# KranPowerV1_3.net
KiCad netlist of a schematic drawn in EAGLE
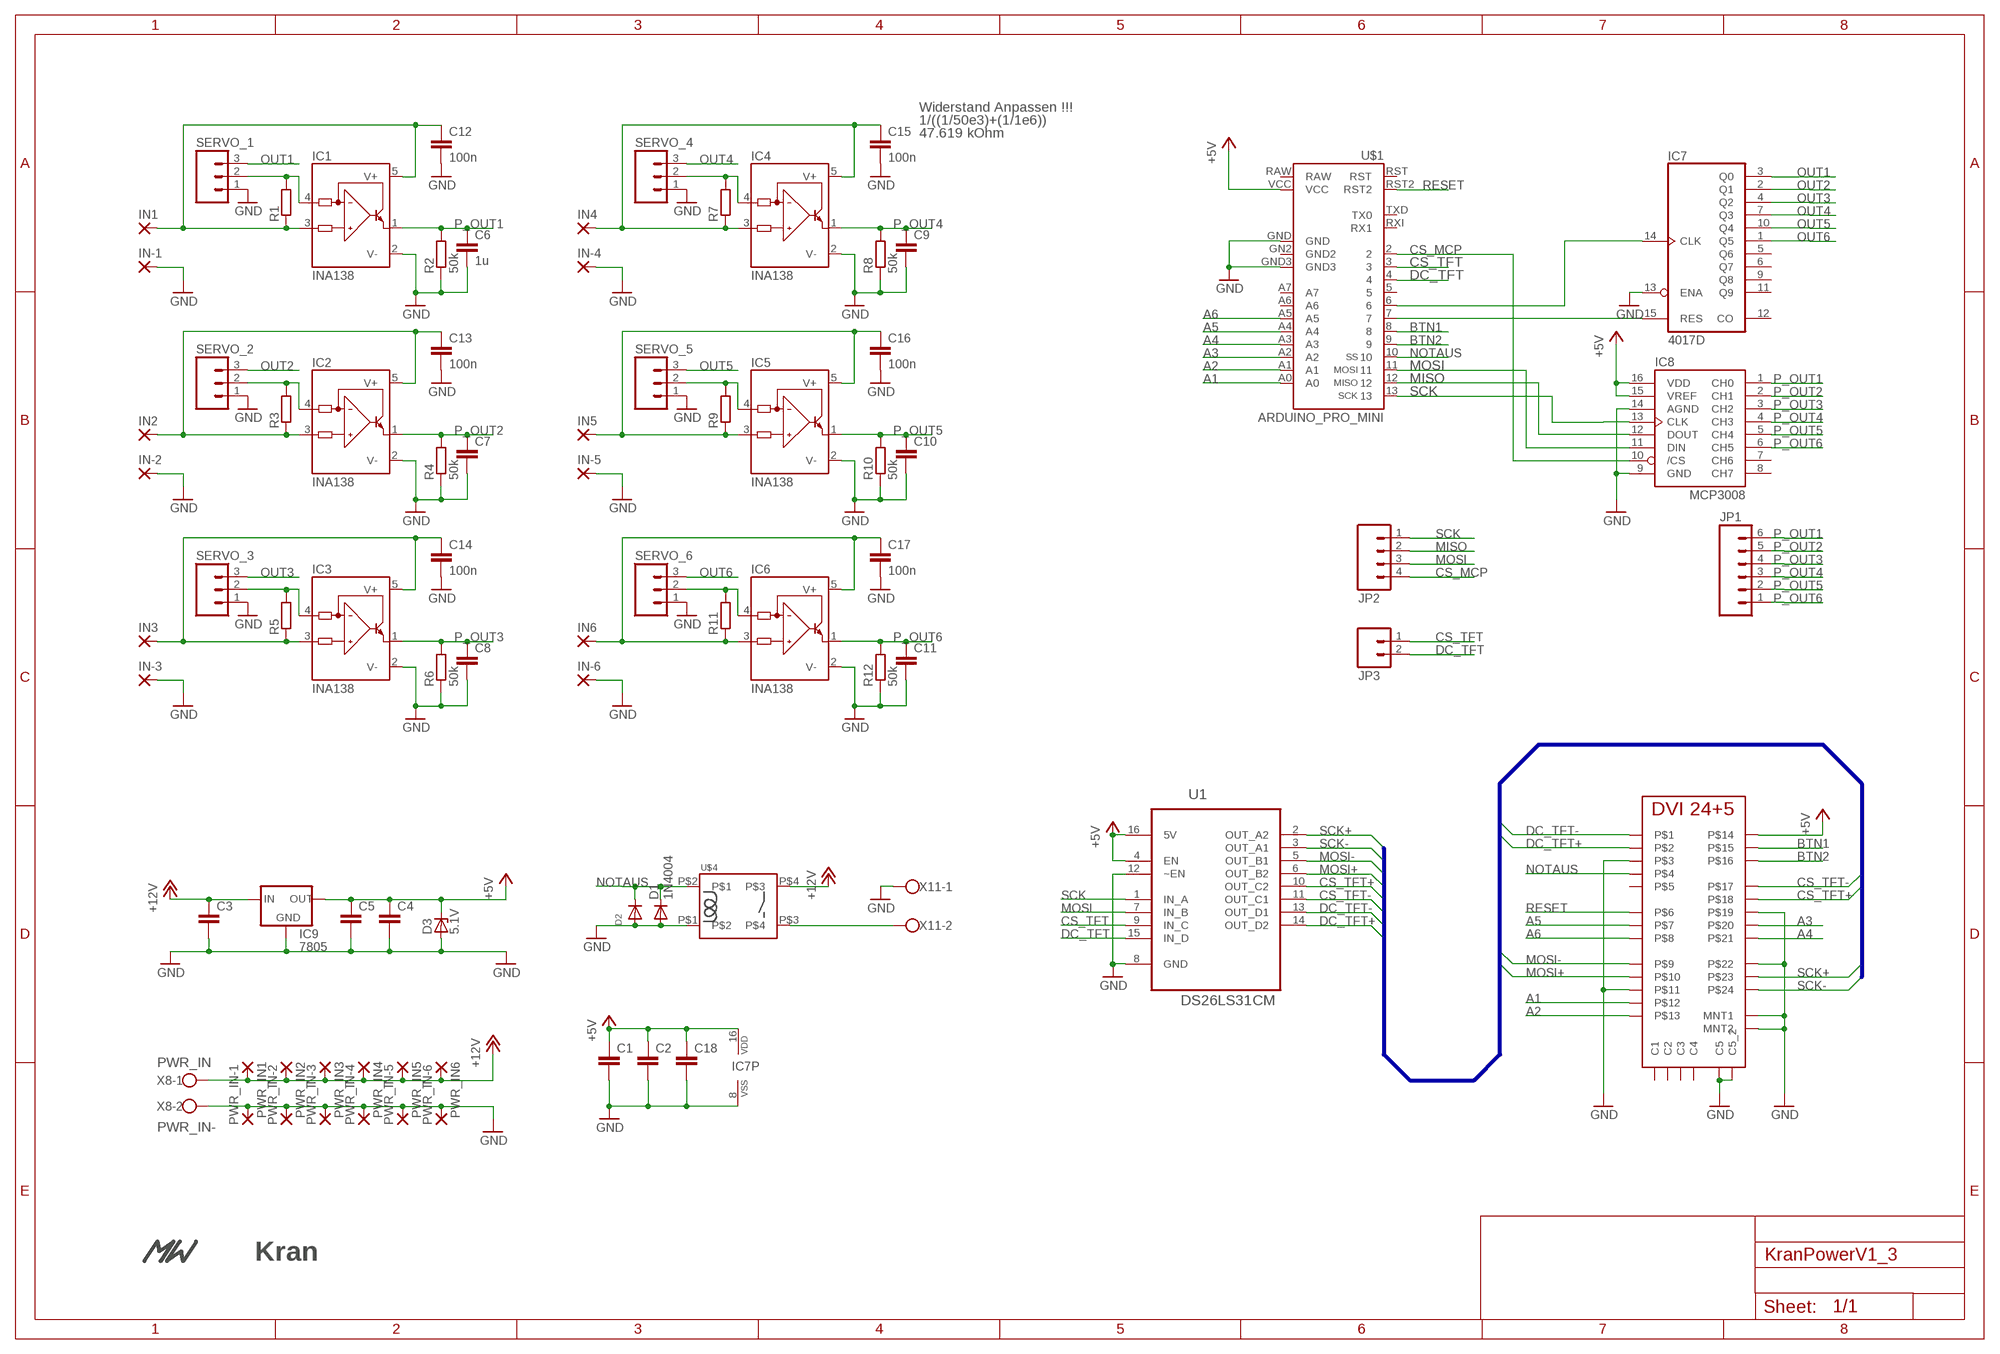
[diagram p0: schematic, sheet 1]

(export (version "E")
  (design (tool "Eeschema 10.0.6"))
  (components
    (comp (ref "C1")
      (value "C-EUC0603")
      (footprint "eagle-import:C0603")
      (libsource (lib "eagle-import") (part "C-EUC0603"))
    )
    (comp (ref "C2")
      (value "C-EUC0603")
      (footprint "eagle-import:C0603")
      (libsource (lib "eagle-import") (part "C-EUC0603"))
    )
    (comp (ref "C3")
      (value "C-EUC0603")
      (footprint "eagle-import:C0603")
      (libsource (lib "eagle-import") (part "C-EUC0603"))
    )
    (comp (ref "C4")
      (value "C-EUC0603")
      (footprint "eagle-import:C0603")
      (libsource (lib "eagle-import") (part "C-EUC0603"))
    )
    (comp (ref "C5")
      (value "C-EUC1206")
      (footprint "eagle-import:C1206")
      (libsource (lib "eagle-import") (part "C-EUC1206"))
    )
    (comp (ref "C6")
      (value "1u")
      (footprint "eagle-import:C0603")
      (libsource (lib "eagle-import") (part "C-EUC0603"))
    )
    (comp (ref "C7")
      (value "C-EUC0603")
      (footprint "eagle-import:C0603")
      (libsource (lib "eagle-import") (part "C-EUC0603"))
    )
    (comp (ref "C8")
      (value "C-EUC0603")
      (footprint "eagle-import:C0603")
      (libsource (lib "eagle-import") (part "C-EUC0603"))
    )
    (comp (ref "C9")
      (value "C-EUC0603")
      (footprint "eagle-import:C0603")
      (libsource (lib "eagle-import") (part "C-EUC0603"))
    )
    (comp (ref "C10")
      (value "C-EUC0603")
      (footprint "eagle-import:C0603")
      (libsource (lib "eagle-import") (part "C-EUC0603"))
    )
    (comp (ref "C11")
      (value "C-EUC0603")
      (footprint "eagle-import:C0603")
      (libsource (lib "eagle-import") (part "C-EUC0603"))
    )
    (comp (ref "C12")
      (value "100n")
      (footprint "eagle-import:C0603")
      (libsource (lib "eagle-import") (part "C-EUC0603"))
    )
    (comp (ref "C13")
      (value "100n")
      (footprint "eagle-import:C0603")
      (libsource (lib "eagle-import") (part "C-EUC0603"))
    )
    (comp (ref "C14")
      (value "100n")
      (footprint "eagle-import:C0603")
      (libsource (lib "eagle-import") (part "C-EUC0603"))
    )
    (comp (ref "C15")
      (value "100n")
      (footprint "eagle-import:C0603")
      (libsource (lib "eagle-import") (part "C-EUC0603"))
    )
    (comp (ref "C16")
      (value "100n")
      (footprint "eagle-import:C0603")
      (libsource (lib "eagle-import") (part "C-EUC0603"))
    )
    (comp (ref "C17")
      (value "100n")
      (footprint "eagle-import:C0603")
      (libsource (lib "eagle-import") (part "C-EUC0603"))
    )
    (comp (ref "C18")
      (value "C-EUC0603")
      (footprint "eagle-import:C0603")
      (libsource (lib "eagle-import") (part "C-EUC0603"))
    )
    (comp (ref "D1")
      (value "1N4004")
      (footprint "eagle-import:DO41-10")
      (libsource (lib "eagle-import") (part "1N4004"))
    )
    (comp (ref "D2")
      (value "DIODESMA")
      (footprint "eagle-import:SMADIODE")
      (libsource (lib "eagle-import") (part "DIODESMA"))
    )
    (comp (ref "D3")
      (value "5.1V")
      (footprint "eagle-import:DO34Z7")
      (libsource (lib "eagle-import") (part "ZENER-DIODEDO34-7"))
    )
    (comp (ref "IC1")
      (value "INA138")
      (footprint "eagle-import:SOT23-5")
      (fields (field (name "MF") "TEXAS INSTRUMENTS") (field (name "MPN") "INA138NA/250"))
      (libsource (lib "eagle-import") (part "INA138"))
    )
    (comp (ref "IC2")
      (value "INA138")
      (footprint "eagle-import:SOT23-5")
      (fields (field (name "MF") "TEXAS INSTRUMENTS") (field (name "MPN") "INA138NA/250"))
      (libsource (lib "eagle-import") (part "INA138"))
    )
    (comp (ref "IC3")
      (value "INA138")
      (footprint "eagle-import:SOT23-5")
      (fields (field (name "MF") "TEXAS INSTRUMENTS") (field (name "MPN") "INA138NA/250"))
      (libsource (lib "eagle-import") (part "INA138"))
    )
    (comp (ref "IC4")
      (value "INA138")
      (footprint "eagle-import:SOT23-5")
      (fields (field (name "MF") "TEXAS INSTRUMENTS") (field (name "MPN") "INA138NA/250"))
      (libsource (lib "eagle-import") (part "INA138"))
    )
    (comp (ref "IC5")
      (value "INA138")
      (footprint "eagle-import:SOT23-5")
      (fields (field (name "MF") "TEXAS INSTRUMENTS") (field (name "MPN") "INA138NA/250"))
      (libsource (lib "eagle-import") (part "INA138"))
    )
    (comp (ref "IC6")
      (value "INA138")
      (footprint "eagle-import:SOT23-5")
      (fields (field (name "MF") "TEXAS INSTRUMENTS") (field (name "MPN") "INA138NA/250"))
      (libsource (lib "eagle-import") (part "INA138"))
    )
    (comp (ref "IC7")
      (value "4017D")
      (footprint "eagle-import:SO16")
      (libsource (lib "eagle-import") (part "4017D"))
    )
    (comp (ref "IC8")
      (value "MCP3008")
      (footprint "eagle-import:SO16")
      (libsource (lib "eagle-import") (part "MCP3008"))
    )
    (comp (ref "IC9")
      (value "7805")
      (footprint "eagle-import:78XXL")
      (libsource (lib "eagle-import") (part "V_REG_78XXSIDE"))
    )
    (comp (ref "IN-1")
      (value "3,81/1,3")
      (footprint "eagle-import:3,81_1,3")
      (libsource (lib "eagle-import") (part "3,81/1,3"))
    )
    (comp (ref "IN-2")
      (value "3,81/1,3")
      (footprint "eagle-import:3,81_1,3")
      (libsource (lib "eagle-import") (part "3,81/1,3"))
    )
    (comp (ref "IN-3")
      (value "3,81/1,3")
      (footprint "eagle-import:3,81_1,3")
      (libsource (lib "eagle-import") (part "3,81/1,3"))
    )
    (comp (ref "IN-4")
      (value "3,81/1,3")
      (footprint "eagle-import:3,81_1,3")
      (libsource (lib "eagle-import") (part "3,81/1,3"))
    )
    (comp (ref "IN-5")
      (value "3,81/1,3")
      (footprint "eagle-import:3,81_1,3")
      (libsource (lib "eagle-import") (part "3,81/1,3"))
    )
    (comp (ref "IN-6")
      (value "3,81/1,3")
      (footprint "eagle-import:3,81_1,3")
      (libsource (lib "eagle-import") (part "3,81/1,3"))
    )
    (comp (ref "IN1")
      (value "3,81/1,3")
      (footprint "eagle-import:3,81_1,3")
      (libsource (lib "eagle-import") (part "3,81/1,3"))
    )
    (comp (ref "IN2")
      (value "3,81/1,3")
      (footprint "eagle-import:3,81_1,3")
      (libsource (lib "eagle-import") (part "3,81/1,3"))
    )
    (comp (ref "IN3")
      (value "3,81/1,3")
      (footprint "eagle-import:3,81_1,3")
      (libsource (lib "eagle-import") (part "3,81/1,3"))
    )
    (comp (ref "IN4")
      (value "3,81/1,3")
      (footprint "eagle-import:3,81_1,3")
      (libsource (lib "eagle-import") (part "3,81/1,3"))
    )
    (comp (ref "IN5")
      (value "3,81/1,3")
      (footprint "eagle-import:3,81_1,3")
      (libsource (lib "eagle-import") (part "3,81/1,3"))
    )
    (comp (ref "IN6")
      (value "3,81/1,3")
      (footprint "eagle-import:3,81_1,3")
      (libsource (lib "eagle-import") (part "3,81/1,3"))
    )
    (comp (ref "JP1")
      (value "M06LOCK")
      (footprint "eagle-import:1X06_LOCK")
      (libsource (lib "eagle-import") (part "M06LOCK"))
    )
    (comp (ref "JP2")
      (value "M04LOCK")
      (footprint "eagle-import:1X04_LOCK")
      (libsource (lib "eagle-import") (part "M04LOCK"))
    )
    (comp (ref "JP3")
      (value "M02LOCK")
      (footprint "eagle-import:1X02_LOCK")
      (libsource (lib "eagle-import") (part "M02LOCK"))
    )
    (comp (ref "PWR_IN-1")
      (value "3,81/1,3")
      (footprint "eagle-import:3,81_1,3")
      (libsource (lib "eagle-import") (part "3,81/1,3"))
    )
    (comp (ref "PWR_IN-2")
      (value "3,81/1,3")
      (footprint "eagle-import:3,81_1,3")
      (libsource (lib "eagle-import") (part "3,81/1,3"))
    )
    (comp (ref "PWR_IN-3")
      (value "3,81/1,3")
      (footprint "eagle-import:3,81_1,3")
      (libsource (lib "eagle-import") (part "3,81/1,3"))
    )
    (comp (ref "PWR_IN-4")
      (value "3,81/1,3")
      (footprint "eagle-import:3,81_1,3")
      (libsource (lib "eagle-import") (part "3,81/1,3"))
    )
    (comp (ref "PWR_IN-5")
      (value "3,81/1,3")
      (footprint "eagle-import:3,81_1,3")
      (libsource (lib "eagle-import") (part "3,81/1,3"))
    )
    (comp (ref "PWR_IN-6")
      (value "3,81/1,3")
      (footprint "eagle-import:3,81_1,3")
      (libsource (lib "eagle-import") (part "3,81/1,3"))
    )
    (comp (ref "PWR_IN1")
      (value "3,81/1,3")
      (footprint "eagle-import:3,81_1,3")
      (libsource (lib "eagle-import") (part "3,81/1,3"))
    )
    (comp (ref "PWR_IN2")
      (value "3,81/1,3")
      (footprint "eagle-import:3,81_1,3")
      (libsource (lib "eagle-import") (part "3,81/1,3"))
    )
    (comp (ref "PWR_IN3")
      (value "3,81/1,3")
      (footprint "eagle-import:3,81_1,3")
      (libsource (lib "eagle-import") (part "3,81/1,3"))
    )
    (comp (ref "PWR_IN4")
      (value "3,81/1,3")
      (footprint "eagle-import:3,81_1,3")
      (libsource (lib "eagle-import") (part "3,81/1,3"))
    )
    (comp (ref "PWR_IN5")
      (value "3,81/1,3")
      (footprint "eagle-import:3,81_1,3")
      (libsource (lib "eagle-import") (part "3,81/1,3"))
    )
    (comp (ref "PWR_IN6")
      (value "3,81/1,3")
      (footprint "eagle-import:3,81_1,3")
      (libsource (lib "eagle-import") (part "3,81/1,3"))
    )
    (comp (ref "R1")
      (value "R-EU_R2512")
      (footprint "eagle-import:R2512")
      (libsource (lib "eagle-import") (part "R-EU_R2512"))
    )
    (comp (ref "R2")
      (value "50k")
      (footprint "eagle-import:R0603")
      (libsource (lib "eagle-import") (part "R-EU_R0603"))
    )
    (comp (ref "R3")
      (value "R-EU_R2512")
      (footprint "eagle-import:R2512")
      (libsource (lib "eagle-import") (part "R-EU_R2512"))
    )
    (comp (ref "R4")
      (value "50k")
      (footprint "eagle-import:R0603")
      (libsource (lib "eagle-import") (part "R-EU_R0603"))
    )
    (comp (ref "R5")
      (value "R-EU_R2512")
      (footprint "eagle-import:R2512")
      (libsource (lib "eagle-import") (part "R-EU_R2512"))
    )
    (comp (ref "R6")
      (value "50k")
      (footprint "eagle-import:R0603")
      (libsource (lib "eagle-import") (part "R-EU_R0603"))
    )
    (comp (ref "R7")
      (value "R-EU_R2512")
      (footprint "eagle-import:R2512")
      (libsource (lib "eagle-import") (part "R-EU_R2512"))
    )
    (comp (ref "R8")
      (value "50k")
      (footprint "eagle-import:R0603")
      (libsource (lib "eagle-import") (part "R-EU_R0603"))
    )
    (comp (ref "R9")
      (value "R-EU_R2512")
      (footprint "eagle-import:R2512")
      (libsource (lib "eagle-import") (part "R-EU_R2512"))
    )
    (comp (ref "R10")
      (value "50k")
      (footprint "eagle-import:R0603")
      (libsource (lib "eagle-import") (part "R-EU_R0603"))
    )
    (comp (ref "R11")
      (value "R-EU_R2512")
      (footprint "eagle-import:R2512")
      (libsource (lib "eagle-import") (part "R-EU_R2512"))
    )
    (comp (ref "R12")
      (value "50k")
      (footprint "eagle-import:R0603")
      (libsource (lib "eagle-import") (part "R-EU_R0603"))
    )
    (comp (ref "SERVO_1")
      (value "M03LOCK")
      (footprint "eagle-import:1X03_LOCK")
      (libsource (lib "eagle-import") (part "M03LOCK"))
    )
    (comp (ref "SERVO_2")
      (value "M03LOCK")
      (footprint "eagle-import:1X03_LOCK")
      (libsource (lib "eagle-import") (part "M03LOCK"))
    )
    (comp (ref "SERVO_3")
      (value "M03LOCK")
      (footprint "eagle-import:1X03_LOCK")
      (libsource (lib "eagle-import") (part "M03LOCK"))
    )
    (comp (ref "SERVO_4")
      (value "M03LOCK")
      (footprint "eagle-import:1X03_LOCK")
      (libsource (lib "eagle-import") (part "M03LOCK"))
    )
    (comp (ref "SERVO_5")
      (value "M03LOCK")
      (footprint "eagle-import:1X03_LOCK")
      (libsource (lib "eagle-import") (part "M03LOCK"))
    )
    (comp (ref "SERVO_6")
      (value "M03LOCK")
      (footprint "eagle-import:1X03_LOCK")
      (libsource (lib "eagle-import") (part "M03LOCK"))
    )
    (comp (ref "U$1")
      (value "ARDUINO_PRO_MINI")
      (footprint "eagle-import:ARDUINO_PRO_MINI")
      (libsource (lib "eagle-import") (part "ARDUINO_PRO_MINI"))
    )
    (comp (ref "U$2")
      (value "MW_LOGO")
      (footprint "eagle-import:MW_11X5MM")
      (libsource (lib "eagle-import") (part "MW_LOGO"))
    )
    (comp (ref "U$3")
      (value "KRAN_LOGO")
      (footprint "eagle-import:KRAN_LOGO")
      (libsource (lib "eagle-import") (part "KRAN_LOGO"))
    )
    (comp (ref "U$4")
      (value "RELAY_ZETTLER_AZ767")
      (footprint "eagle-import:RELAY_ZETTLER_AZ767")
      (libsource (lib "eagle-import") (part "RELAY_ZETTLER_AZ767"))
    )
    (comp (ref "U$11")
      (value "DVI_BUCHSE")
      (footprint "eagle-import:DVI_BUCHSE")
      (libsource (lib "eagle-import") (part "DVI_BUCHSE"))
    )
    (comp (ref "U1")
      (value "DS26LS31CM")
      (footprint "eagle-import:SOIC127P600X175-16N")
      (libsource (lib "eagle-import") (part "DS26LS31CM"))
    )
    (comp (ref "X8")
      (value "W237-102")
      (footprint "eagle-import:W237-102")
      (fields (field (name "MPN") "237-102"))
      (libsource (lib "eagle-import") (part "W237-102"))
    )
    (comp (ref "X11")
      (value "W237-102")
      (footprint "eagle-import:W237-102")
      (fields (field (name "MPN") "237-102"))
      (libsource (lib "eagle-import") (part "W237-102"))
    )
  )
  (nets
    (net (code "1") (name "+5V") (class "Default")
      (node (ref "C1") (pin "1") (pinfunction "1_1") (pintype "passive"))
      (node (ref "C18") (pin "1") (pinfunction "1_1") (pintype "passive"))
      (node (ref "C2") (pin "1") (pinfunction "1_1") (pintype "passive"))
      (node (ref "C4") (pin "1") (pinfunction "1_1") (pintype "passive"))
      (node (ref "C5") (pin "1") (pinfunction "1_1") (pintype "passive"))
      (node (ref "D3") (pin "C") (pinfunction "C_C") (pintype "passive"))
      (node (ref "IC7") (pin "16") (pinfunction "VDD_16") (pintype "power_in"))
      (node (ref "IC8") (pin "15") (pinfunction "VREF_15") (pintype "input"))
      (node (ref "IC8") (pin "16") (pinfunction "VDD_16") (pintype "power_in"))
      (node (ref "IC9") (pin "OUT") (pinfunction "OUT_OUT") (pintype "output"))
      (node (ref "U$1") (pin "VCC") (pinfunction "VCC_VCC") (pintype "bidirectional"))
      (node (ref "U$11") (pin "P$14") (pinfunction "P$14_P$14") (pintype "bidirectional"))
      (node (ref "U1") (pin "16") (pinfunction "5V_16") (pintype "power_in"))
      (node (ref "U1") (pin "4") (pinfunction "EN_4") (pintype "input"))
    )
    (net (code "2") (name "+12V") (class "Default")
      (node (ref "C3") (pin "1") (pinfunction "1_1") (pintype "passive"))
      (node (ref "IC9") (pin "IN") (pinfunction "IN_IN") (pintype "input"))
      (node (ref "PWR_IN1") (pin "1") (pinfunction "P_1") (pintype "passive"))
      (node (ref "PWR_IN2") (pin "1") (pinfunction "P_1") (pintype "passive"))
      (node (ref "PWR_IN3") (pin "1") (pinfunction "P_1") (pintype "passive"))
      (node (ref "PWR_IN4") (pin "1") (pinfunction "P_1") (pintype "passive"))
      (node (ref "PWR_IN5") (pin "1") (pinfunction "P_1") (pintype "passive"))
      (node (ref "PWR_IN6") (pin "1") (pinfunction "P_1") (pintype "passive"))
      (node (ref "U$4") (pin "P$4") (pinfunction "P$3_P$4") (pintype "bidirectional"))
      (node (ref "X8") (pin "1") (pinfunction "KL_1") (pintype "passive"))
    )
    (net (code "3") (name "/A1") (class "Default")
      (node (ref "U$1") (pin "A0") (pinfunction "A0_A0") (pintype "bidirectional"))
      (node (ref "U$11") (pin "P$12") (pinfunction "P$12_P$12") (pintype "bidirectional"))
    )
    (net (code "4") (name "/A2") (class "Default")
      (node (ref "U$1") (pin "A1") (pinfunction "A1_A1") (pintype "bidirectional"))
      (node (ref "U$11") (pin "P$13") (pinfunction "P$13_P$13") (pintype "bidirectional"))
    )
    (net (code "5") (name "/A3") (class "Default")
      (node (ref "U$1") (pin "A2") (pinfunction "A2_A2") (pintype "bidirectional"))
      (node (ref "U$11") (pin "P$4") (pinfunction "P$20_P$4") (pintype "bidirectional"))
    )
    (net (code "6") (name "/A4") (class "Default")
      (node (ref "U$1") (pin "A3") (pinfunction "A3_A3") (pintype "bidirectional"))
      (node (ref "U$11") (pin "P$5") (pinfunction "P$21_P$5") (pintype "bidirectional"))
    )
    (net (code "7") (name "/A5") (class "Default")
      (node (ref "U$1") (pin "A4") (pinfunction "A4_A4") (pintype "bidirectional"))
      (node (ref "U$11") (pin "P$23") (pinfunction "P$7_P$23") (pintype "bidirectional"))
    )
    (net (code "8") (name "/A6") (class "Default")
      (node (ref "U$1") (pin "A5") (pinfunction "A5_A5") (pintype "bidirectional"))
      (node (ref "U$11") (pin "P$24") (pinfunction "P$8_P$24") (pintype "bidirectional"))
    )
    (net (code "9") (name "/BTN1") (class "Default")
      (node (ref "U$1") (pin "8") (pinfunction "8_8") (pintype "bidirectional"))
      (node (ref "U$11") (pin "P$15") (pinfunction "P$15_P$15") (pintype "bidirectional"))
    )
    (net (code "10") (name "/BTN2") (class "Default")
      (node (ref "U$1") (pin "9") (pinfunction "9_9") (pintype "bidirectional"))
      (node (ref "U$11") (pin "P$16") (pinfunction "P$16_P$16") (pintype "bidirectional"))
    )
    (net (code "11") (name "/CS_MCP") (class "Default")
      (node (ref "IC8") (pin "10") (pinfunction "/CS_10") (pintype "input"))
      (node (ref "JP2") (pin "4") (pinfunction "4_4") (pintype "passive"))
      (node (ref "U$1") (pin "2") (pinfunction "2_2") (pintype "bidirectional"))
    )
    (net (code "12") (name "/CS_TFT") (class "Default")
      (node (ref "JP3") (pin "1") (pinfunction "1_1") (pintype "passive"))
      (node (ref "U$1") (pin "3") (pinfunction "3_3") (pintype "bidirectional"))
      (node (ref "U1") (pin "9") (pinfunction "IN_C_9") (pintype "input"))
    )
    (net (code "13") (name "/CS_TFT+") (class "Default")
      (node (ref "U$11") (pin "P$2") (pinfunction "P$18_P$2") (pintype "bidirectional"))
      (node (ref "U1") (pin "10") (pinfunction "OUT_C2_10") (pintype "output"))
    )
    (net (code "14") (name "/CS_TFT-") (class "Default")
      (node (ref "U$11") (pin "P$1") (pinfunction "P$17_P$1") (pintype "bidirectional"))
      (node (ref "U1") (pin "11") (pinfunction "OUT_C1_11") (pintype "output"))
    )
    (net (code "15") (name "/DC_TFT") (class "Default")
      (node (ref "JP3") (pin "2") (pinfunction "2_2") (pintype "passive"))
      (node (ref "U$1") (pin "4") (pinfunction "4_4") (pintype "bidirectional"))
      (node (ref "U1") (pin "15") (pinfunction "IN_D_15") (pintype "input"))
    )
    (net (code "16") (name "/DC_TFT+") (class "Default")
      (node (ref "U$11") (pin "P$18") (pinfunction "P$2_P$18") (pintype "bidirectional"))
      (node (ref "U1") (pin "14") (pinfunction "OUT_D2_14") (pintype "output"))
    )
    (net (code "17") (name "/DC_TFT-") (class "Default")
      (node (ref "U$11") (pin "P$17") (pinfunction "P$1_P$17") (pintype "bidirectional"))
      (node (ref "U1") (pin "13") (pinfunction "OUT_D1_13") (pintype "output"))
    )
    (net (code "18") (name "/MISO") (class "Default")
      (node (ref "IC8") (pin "12") (pinfunction "DOUT_12") (pintype "output"))
      (node (ref "JP2") (pin "2") (pinfunction "2_2") (pintype "passive"))
      (node (ref "U$1") (pin "12") (pinfunction "12_12") (pintype "bidirectional"))
    )
    (net (code "19") (name "/MOSI") (class "Default")
      (node (ref "IC8") (pin "11") (pinfunction "DIN_11") (pintype "input"))
      (node (ref "JP2") (pin "3") (pinfunction "3_3") (pintype "passive"))
      (node (ref "U$1") (pin "11") (pinfunction "11_11") (pintype "bidirectional"))
      (node (ref "U1") (pin "7") (pinfunction "IN_B_7") (pintype "input"))
    )
    (net (code "20") (name "/MOSI+") (class "Default")
      (node (ref "U$11") (pin "P$10") (pinfunction "P$10_P$10") (pintype "bidirectional"))
      (node (ref "U1") (pin "6") (pinfunction "OUT_B2_6") (pintype "output"))
    )
    (net (code "21") (name "/MOSI-") (class "Default")
      (node (ref "U$11") (pin "P$9") (pinfunction "P$9_P$9") (pintype "bidirectional"))
      (node (ref "U1") (pin "5") (pinfunction "OUT_B1_5") (pintype "output"))
    )
    (net (code "22") (name "/NOTAUS") (class "Default")
      (node (ref "D1") (pin "C") (pinfunction "C_C") (pintype "passive"))
      (node (ref "D2") (pin "C") (pinfunction "C_C") (pintype "passive"))
      (node (ref "U$1") (pin "10") (pinfunction "10_10") (pintype "bidirectional"))
      (node (ref "U$11") (pin "P$20") (pinfunction "P$4_P$20") (pintype "bidirectional"))
      (node (ref "U$4") (pin "P$2") (pinfunction "P$1_P$2") (pintype "bidirectional"))
    )
    (net (code "23") (name "/OUT1") (class "Default")
      (node (ref "IC7") (pin "3") (pinfunction "Q0_3") (pintype "output"))
      (node (ref "SERVO_1") (pin "3") (pinfunction "3_3") (pintype "passive"))
    )
    (net (code "24") (name "/OUT2") (class "Default")
      (node (ref "IC7") (pin "2") (pinfunction "Q1_2") (pintype "output"))
      (node (ref "SERVO_2") (pin "3") (pinfunction "3_3") (pintype "passive"))
    )
    (net (code "25") (name "/OUT3") (class "Default")
      (node (ref "IC7") (pin "4") (pinfunction "Q2_4") (pintype "output"))
      (node (ref "SERVO_3") (pin "3") (pinfunction "3_3") (pintype "passive"))
    )
    (net (code "26") (name "/OUT4") (class "Default")
      (node (ref "IC7") (pin "7") (pinfunction "Q3_7") (pintype "output"))
      (node (ref "SERVO_4") (pin "3") (pinfunction "3_3") (pintype "passive"))
    )
    (net (code "27") (name "/OUT5") (class "Default")
      (node (ref "IC7") (pin "10") (pinfunction "Q4_10") (pintype "output"))
      (node (ref "SERVO_5") (pin "3") (pinfunction "3_3") (pintype "passive"))
    )
    (net (code "28") (name "/OUT6") (class "Default")
      (node (ref "IC7") (pin "1") (pinfunction "Q5_1") (pintype "output"))
      (node (ref "SERVO_6") (pin "3") (pinfunction "3_3") (pintype "passive"))
    )
    (net (code "29") (name "/P_OUT1") (class "Default")
      (node (ref "C6") (pin "1") (pinfunction "1_1") (pintype "passive"))
      (node (ref "IC1") (pin "1") (pinfunction "OUT_1") (pintype "output"))
      (node (ref "IC8") (pin "1") (pinfunction "CH0_1") (pintype "input"))
      (node (ref "JP1") (pin "6") (pinfunction "6_6") (pintype "passive"))
      (node (ref "R2") (pin "2") (pinfunction "2_2") (pintype "passive"))
    )
    (net (code "30") (name "/P_OUT2") (class "Default")
      (node (ref "C7") (pin "1") (pinfunction "1_1") (pintype "passive"))
      (node (ref "IC2") (pin "1") (pinfunction "OUT_1") (pintype "output"))
      (node (ref "IC8") (pin "2") (pinfunction "CH1_2") (pintype "input"))
      (node (ref "JP1") (pin "5") (pinfunction "5_5") (pintype "passive"))
      (node (ref "R4") (pin "2") (pinfunction "2_2") (pintype "passive"))
    )
    (net (code "31") (name "/P_OUT3") (class "Default")
      (node (ref "C8") (pin "1") (pinfunction "1_1") (pintype "passive"))
      (node (ref "IC3") (pin "1") (pinfunction "OUT_1") (pintype "output"))
      (node (ref "IC8") (pin "3") (pinfunction "CH2_3") (pintype "input"))
      (node (ref "JP1") (pin "4") (pinfunction "4_4") (pintype "passive"))
      (node (ref "R6") (pin "2") (pinfunction "2_2") (pintype "passive"))
    )
    (net (code "32") (name "/P_OUT4") (class "Default")
      (node (ref "C9") (pin "1") (pinfunction "1_1") (pintype "passive"))
      (node (ref "IC4") (pin "1") (pinfunction "OUT_1") (pintype "output"))
      (node (ref "IC8") (pin "4") (pinfunction "CH3_4") (pintype "input"))
      (node (ref "JP1") (pin "3") (pinfunction "3_3") (pintype "passive"))
      (node (ref "R8") (pin "2") (pinfunction "2_2") (pintype "passive"))
    )
    (net (code "33") (name "/P_OUT5") (class "Default")
      (node (ref "C10") (pin "1") (pinfunction "1_1") (pintype "passive"))
      (node (ref "IC5") (pin "1") (pinfunction "OUT_1") (pintype "output"))
      (node (ref "IC8") (pin "5") (pinfunction "CH4_5") (pintype "input"))
      (node (ref "JP1") (pin "2") (pinfunction "2_2") (pintype "passive"))
      (node (ref "R10") (pin "2") (pinfunction "2_2") (pintype "passive"))
    )
    (net (code "34") (name "/P_OUT6") (class "Default")
      (node (ref "C11") (pin "1") (pinfunction "1_1") (pintype "passive"))
      (node (ref "IC6") (pin "1") (pinfunction "OUT_1") (pintype "output"))
      (node (ref "IC8") (pin "6") (pinfunction "CH5_6") (pintype "input"))
      (node (ref "JP1") (pin "1") (pinfunction "1_1") (pintype "passive"))
      (node (ref "R12") (pin "2") (pinfunction "2_2") (pintype "passive"))
    )
    (net (code "35") (name "/RESET") (class "Default")
      (node (ref "U$1") (pin "RST2") (pinfunction "RST2_RST2") (pintype "bidirectional"))
      (node (ref "U$11") (pin "P$22") (pinfunction "P$6_P$22") (pintype "bidirectional"))
    )
    (net (code "36") (name "/SCK") (class "Default")
      (node (ref "IC8") (pin "13") (pinfunction "CLK_13") (pintype "input"))
      (node (ref "JP2") (pin "1") (pinfunction "1_1") (pintype "passive"))
      (node (ref "U$1") (pin "13") (pinfunction "13_13") (pintype "bidirectional"))
      (node (ref "U1") (pin "1") (pinfunction "IN_A_1") (pintype "input"))
    )
    (net (code "37") (name "/SCK+") (class "Default")
      (node (ref "U$11") (pin "P$7") (pinfunction "P$23_P$7") (pintype "bidirectional"))
      (node (ref "U1") (pin "2") (pinfunction "OUT_A2_2") (pintype "output"))
    )
    (net (code "38") (name "/SCK-") (class "Default")
      (node (ref "U$11") (pin "P$8") (pinfunction "P$24_P$8") (pintype "bidirectional"))
      (node (ref "U1") (pin "3") (pinfunction "OUT_A1_3") (pintype "output"))
    )
    (net (code "39") (name "GND") (class "Default")
      (node (ref "C1") (pin "2") (pinfunction "2_2") (pintype "passive"))
      (node (ref "C10") (pin "2") (pinfunction "2_2") (pintype "passive"))
      (node (ref "C11") (pin "2") (pinfunction "2_2") (pintype "passive"))
      (node (ref "C12") (pin "2") (pinfunction "2_2") (pintype "passive"))
      (node (ref "C13") (pin "2") (pinfunction "2_2") (pintype "passive"))
      (node (ref "C14") (pin "2") (pinfunction "2_2") (pintype "passive"))
      (node (ref "C15") (pin "2") (pinfunction "2_2") (pintype "passive"))
      (node (ref "C16") (pin "2") (pinfunction "2_2") (pintype "passive"))
      (node (ref "C17") (pin "2") (pinfunction "2_2") (pintype "passive"))
      (node (ref "C18") (pin "2") (pinfunction "2_2") (pintype "passive"))
      (node (ref "C2") (pin "2") (pinfunction "2_2") (pintype "passive"))
      (node (ref "C3") (pin "2") (pinfunction "2_2") (pintype "passive"))
      (node (ref "C4") (pin "2") (pinfunction "2_2") (pintype "passive"))
      (node (ref "C5") (pin "2") (pinfunction "2_2") (pintype "passive"))
      (node (ref "C6") (pin "2") (pinfunction "2_2") (pintype "passive"))
      (node (ref "C7") (pin "2") (pinfunction "2_2") (pintype "passive"))
      (node (ref "C8") (pin "2") (pinfunction "2_2") (pintype "passive"))
      (node (ref "C9") (pin "2") (pinfunction "2_2") (pintype "passive"))
      (node (ref "D1") (pin "A") (pinfunction "A_A") (pintype "passive"))
      (node (ref "D2") (pin "A") (pinfunction "A_A") (pintype "passive"))
      (node (ref "D3") (pin "A") (pinfunction "A_A") (pintype "passive"))
      (node (ref "IC1") (pin "2") (pinfunction "V-_2") (pintype "power_in"))
      (node (ref "IC2") (pin "2") (pinfunction "V-_2") (pintype "power_in"))
      (node (ref "IC3") (pin "2") (pinfunction "V-_2") (pintype "power_in"))
      (node (ref "IC4") (pin "2") (pinfunction "V-_2") (pintype "power_in"))
      (node (ref "IC5") (pin "2") (pinfunction "V-_2") (pintype "power_in"))
      (node (ref "IC6") (pin "2") (pinfunction "V-_2") (pintype "power_in"))
      (node (ref "IC7") (pin "13") (pinfunction "ENA_13") (pintype "input"))
      (node (ref "IC7") (pin "8") (pinfunction "VSS_8") (pintype "power_in"))
      (node (ref "IC8") (pin "14") (pinfunction "AGND_14") (pintype "power_in"))
      (node (ref "IC8") (pin "9") (pinfunction "GND_9") (pintype "power_in"))
      (node (ref "IC9") (pin "GND") (pinfunction "GND_GND") (pintype "input"))
      (node (ref "IN-1") (pin "1") (pinfunction "P_1") (pintype "passive"))
      (node (ref "IN-2") (pin "1") (pinfunction "P_1") (pintype "passive"))
      (node (ref "IN-3") (pin "1") (pinfunction "P_1") (pintype "passive"))
      (node (ref "IN-4") (pin "1") (pinfunction "P_1") (pintype "passive"))
      (node (ref "IN-5") (pin "1") (pinfunction "P_1") (pintype "passive"))
      (node (ref "IN-6") (pin "1") (pinfunction "P_1") (pintype "passive"))
      (node (ref "PWR_IN-1") (pin "1") (pinfunction "P_1") (pintype "passive"))
      (node (ref "PWR_IN-2") (pin "1") (pinfunction "P_1") (pintype "passive"))
      (node (ref "PWR_IN-3") (pin "1") (pinfunction "P_1") (pintype "passive"))
      (node (ref "PWR_IN-4") (pin "1") (pinfunction "P_1") (pintype "passive"))
      (node (ref "PWR_IN-5") (pin "1") (pinfunction "P_1") (pintype "passive"))
      (node (ref "PWR_IN-6") (pin "1") (pinfunction "P_1") (pintype "passive"))
      (node (ref "R10") (pin "1") (pinfunction "1_1") (pintype "passive"))
      (node (ref "R12") (pin "1") (pinfunction "1_1") (pintype "passive"))
      (node (ref "R2") (pin "1") (pinfunction "1_1") (pintype "passive"))
      (node (ref "R4") (pin "1") (pinfunction "1_1") (pintype "passive"))
      (node (ref "R6") (pin "1") (pinfunction "1_1") (pintype "passive"))
      (node (ref "R8") (pin "1") (pinfunction "1_1") (pintype "passive"))
      (node (ref "SERVO_1") (pin "1") (pinfunction "1_1") (pintype "passive"))
      (node (ref "SERVO_2") (pin "1") (pinfunction "1_1") (pintype "passive"))
      (node (ref "SERVO_3") (pin "1") (pinfunction "1_1") (pintype "passive"))
      (node (ref "SERVO_4") (pin "1") (pinfunction "1_1") (pintype "passive"))
      (node (ref "SERVO_5") (pin "1") (pinfunction "1_1") (pintype "passive"))
      (node (ref "SERVO_6") (pin "1") (pinfunction "1_1") (pintype "passive"))
      (node (ref "U$1") (pin "GND") (pinfunction "GND_GND") (pintype "bidirectional"))
      (node (ref "U$1") (pin "GND3") (pinfunction "GND3_GND3") (pintype "bidirectional"))
      (node (ref "U$11") (pin "MNT1") (pinfunction "MNT1_MNT1") (pintype "bidirectional"))
      (node (ref "U$11") (pin "MNT2") (pinfunction "MNT2_MNT2") (pintype "bidirectional"))
      (node (ref "U$11") (pin "P$11") (pinfunction "P$11_P$11") (pintype "bidirectional"))
      (node (ref "U$11") (pin "P$19") (pinfunction "P$3_P$19") (pintype "bidirectional"))
      (node (ref "U$11") (pin "P$28") (pinfunction "C5_P$28") (pintype "bidirectional"))
      (node (ref "U$11") (pin "P$3") (pinfunction "P$19_P$3") (pintype "bidirectional"))
      (node (ref "U$11") (pin "P$30") (pinfunction "C5_2_P$30") (pintype "bidirectional"))
      (node (ref "U$11") (pin "P$6") (pinfunction "P$22_P$6") (pintype "bidirectional"))
      (node (ref "U$4") (pin "P$1") (pinfunction "P$2_P$1") (pintype "bidirectional"))
      (node (ref "U1") (pin "12") (pinfunction "~{EN}_12") (pintype "input"))
      (node (ref "U1") (pin "8") (pinfunction "GND_8") (pintype "passive"))
      (node (ref "X11") (pin "1") (pinfunction "KL_1") (pintype "passive"))
      (node (ref "X8") (pin "2") (pinfunction "KL_2") (pintype "passive"))
    )
    (net (code "40") (name "Net-(IC1-IN+)") (class "Default")
      (node (ref "C12") (pin "1") (pinfunction "1_1") (pintype "passive"))
      (node (ref "IC1") (pin "3") (pinfunction "IN+_3") (pintype "input"))
      (node (ref "IC1") (pin "5") (pinfunction "V+_5") (pintype "power_in"))
      (node (ref "IN1") (pin "1") (pinfunction "P_1") (pintype "passive"))
      (node (ref "R1") (pin "1") (pinfunction "1_1") (pintype "passive"))
    )
    (net (code "41") (name "Net-(IC1-IN-)") (class "Default")
      (node (ref "IC1") (pin "4") (pinfunction "IN-_4") (pintype "input"))
      (node (ref "R1") (pin "2") (pinfunction "2_2") (pintype "passive"))
      (node (ref "SERVO_1") (pin "2") (pinfunction "2_2") (pintype "passive"))
    )
    (net (code "42") (name "Net-(IC2-IN+)") (class "Default")
      (node (ref "C13") (pin "1") (pinfunction "1_1") (pintype "passive"))
      (node (ref "IC2") (pin "3") (pinfunction "IN+_3") (pintype "input"))
      (node (ref "IC2") (pin "5") (pinfunction "V+_5") (pintype "power_in"))
      (node (ref "IN2") (pin "1") (pinfunction "P_1") (pintype "passive"))
      (node (ref "R3") (pin "1") (pinfunction "1_1") (pintype "passive"))
    )
    (net (code "43") (name "Net-(IC2-IN-)") (class "Default")
      (node (ref "IC2") (pin "4") (pinfunction "IN-_4") (pintype "input"))
      (node (ref "R3") (pin "2") (pinfunction "2_2") (pintype "passive"))
      (node (ref "SERVO_2") (pin "2") (pinfunction "2_2") (pintype "passive"))
    )
    (net (code "44") (name "Net-(IC3-IN+)") (class "Default")
      (node (ref "C14") (pin "1") (pinfunction "1_1") (pintype "passive"))
      (node (ref "IC3") (pin "3") (pinfunction "IN+_3") (pintype "input"))
      (node (ref "IC3") (pin "5") (pinfunction "V+_5") (pintype "power_in"))
      (node (ref "IN3") (pin "1") (pinfunction "P_1") (pintype "passive"))
      (node (ref "R5") (pin "1") (pinfunction "1_1") (pintype "passive"))
    )
    (net (code "45") (name "Net-(IC3-IN-)") (class "Default")
      (node (ref "IC3") (pin "4") (pinfunction "IN-_4") (pintype "input"))
      (node (ref "R5") (pin "2") (pinfunction "2_2") (pintype "passive"))
      (node (ref "SERVO_3") (pin "2") (pinfunction "2_2") (pintype "passive"))
    )
    (net (code "46") (name "Net-(IC4-IN+)") (class "Default")
      (node (ref "C15") (pin "1") (pinfunction "1_1") (pintype "passive"))
      (node (ref "IC4") (pin "3") (pinfunction "IN+_3") (pintype "input"))
      (node (ref "IC4") (pin "5") (pinfunction "V+_5") (pintype "power_in"))
      (node (ref "IN4") (pin "1") (pinfunction "P_1") (pintype "passive"))
      (node (ref "R7") (pin "1") (pinfunction "1_1") (pintype "passive"))
    )
    (net (code "47") (name "Net-(IC4-IN-)") (class "Default")
      (node (ref "IC4") (pin "4") (pinfunction "IN-_4") (pintype "input"))
      (node (ref "R7") (pin "2") (pinfunction "2_2") (pintype "passive"))
      (node (ref "SERVO_4") (pin "2") (pinfunction "2_2") (pintype "passive"))
    )
    (net (code "48") (name "Net-(IC5-IN+)") (class "Default")
      (node (ref "C16") (pin "1") (pinfunction "1_1") (pintype "passive"))
      (node (ref "IC5") (pin "3") (pinfunction "IN+_3") (pintype "input"))
      (node (ref "IC5") (pin "5") (pinfunction "V+_5") (pintype "power_in"))
      (node (ref "IN5") (pin "1") (pinfunction "P_1") (pintype "passive"))
      (node (ref "R9") (pin "1") (pinfunction "1_1") (pintype "passive"))
    )
    (net (code "49") (name "Net-(IC5-IN-)") (class "Default")
      (node (ref "IC5") (pin "4") (pinfunction "IN-_4") (pintype "input"))
      (node (ref "R9") (pin "2") (pinfunction "2_2") (pintype "passive"))
      (node (ref "SERVO_5") (pin "2") (pinfunction "2_2") (pintype "passive"))
    )
    (net (code "50") (name "Net-(IC6-IN+)") (class "Default")
      (node (ref "C17") (pin "1") (pinfunction "1_1") (pintype "passive"))
      (node (ref "IC6") (pin "3") (pinfunction "IN+_3") (pintype "input"))
      (node (ref "IC6") (pin "5") (pinfunction "V+_5") (pintype "power_in"))
      (node (ref "IN6") (pin "1") (pinfunction "P_1") (pintype "passive"))
      (node (ref "R11") (pin "1") (pinfunction "1_1") (pintype "passive"))
    )
    (net (code "51") (name "Net-(IC6-IN-)") (class "Default")
      (node (ref "IC6") (pin "4") (pinfunction "IN-_4") (pintype "input"))
      (node (ref "R11") (pin "2") (pinfunction "2_2") (pintype "passive"))
      (node (ref "SERVO_6") (pin "2") (pinfunction "2_2") (pintype "passive"))
    )
    (net (code "52") (name "Net-(IC7A-CLK)") (class "Default")
      (node (ref "IC7") (pin "14") (pinfunction "CLK_14") (pintype "input"))
      (node (ref "U$1") (pin "6") (pinfunction "6_6") (pintype "bidirectional"))
    )
    (net (code "53") (name "Net-(IC7A-RES)") (class "Default")
      (node (ref "IC7") (pin "15") (pinfunction "RES_15") (pintype "input"))
      (node (ref "U$1") (pin "7") (pinfunction "7_7") (pintype "bidirectional"))
    )
    (net (code "54") (name "Net-(U$4-P$4)") (class "Default")
      (node (ref "U$4") (pin "P$3") (pinfunction "P$4_P$3") (pintype "bidirectional"))
      (node (ref "X11") (pin "2") (pinfunction "KL_2") (pintype "passive"))
    )
    (net (code "55") (name "unconnected-(IC7A-CO-Pad12)") (class "Default")
      (node (ref "IC7") (pin "12") (pinfunction "CO_12") (pintype "output"))
    )
    (net (code "56") (name "unconnected-(IC7A-Q6-Pad5)") (class "Default")
      (node (ref "IC7") (pin "5") (pinfunction "Q6_5") (pintype "output"))
    )
    (net (code "57") (name "unconnected-(IC7A-Q7-Pad6)") (class "Default")
      (node (ref "IC7") (pin "6") (pinfunction "Q7_6") (pintype "output"))
    )
    (net (code "58") (name "unconnected-(IC7A-Q8-Pad9)") (class "Default")
      (node (ref "IC7") (pin "9") (pinfunction "Q8_9") (pintype "output"))
    )
    (net (code "59") (name "unconnected-(IC7A-Q9-Pad11)") (class "Default")
      (node (ref "IC7") (pin "11") (pinfunction "Q9_11") (pintype "output"))
    )
    (net (code "60") (name "unconnected-(IC8-CH6-Pad7)") (class "Default")
      (node (ref "IC8") (pin "7") (pinfunction "CH6_7") (pintype "input"))
    )
    (net (code "61") (name "unconnected-(IC8-CH7-Pad8)") (class "Default")
      (node (ref "IC8") (pin "8") (pinfunction "CH7_8") (pintype "input"))
    )
    (net (code "62") (name "unconnected-(U$1-GND2-PadGN2)") (class "Default")
      (node (ref "U$1") (pin "GN2") (pinfunction "GND2_GN2") (pintype "bidirectional"))
    )
    (net (code "63") (name "unconnected-(U$1-Pad5)") (class "Default")
      (node (ref "U$1") (pin "5") (pinfunction "5_5") (pintype "bidirectional"))
    )
    (net (code "64") (name "unconnected-(U$1-PadA6)") (class "Default")
      (node (ref "U$1") (pin "A6") (pinfunction "A6_A6") (pintype "bidirectional"))
    )
    (net (code "65") (name "unconnected-(U$1-PadA7)") (class "Default")
      (node (ref "U$1") (pin "A7") (pinfunction "A7_A7") (pintype "bidirectional"))
    )
    (net (code "66") (name "unconnected-(U$1-PadRAW)") (class "Default")
      (node (ref "U$1") (pin "RAW") (pinfunction "RAW_RAW") (pintype "bidirectional"))
    )
    (net (code "67") (name "unconnected-(U$1-PadRST)") (class "Default")
      (node (ref "U$1") (pin "RST") (pinfunction "RST_RST") (pintype "bidirectional"))
    )
    (net (code "68") (name "unconnected-(U$1-RX1-PadRXI)") (class "Default")
      (node (ref "U$1") (pin "RXI") (pinfunction "RX1_RXI") (pintype "bidirectional"))
    )
    (net (code "69") (name "unconnected-(U$1-TX0-PadTXD)") (class "Default")
      (node (ref "U$1") (pin "TXD") (pinfunction "TX0_TXD") (pintype "bidirectional"))
    )
    (net (code "70") (name "unconnected-(U$11-C1-PadP$29)") (class "Default")
      (node (ref "U$11") (pin "P$29") (pinfunction "C1_P$29") (pintype "bidirectional"))
    )
    (net (code "71") (name "unconnected-(U$11-C2-PadP$25)") (class "Default")
      (node (ref "U$11") (pin "P$25") (pinfunction "C2_P$25") (pintype "bidirectional"))
    )
    (net (code "72") (name "unconnected-(U$11-C3-PadP$27)") (class "Default")
      (node (ref "U$11") (pin "P$27") (pinfunction "C3_P$27") (pintype "bidirectional"))
    )
    (net (code "73") (name "unconnected-(U$11-C4-PadP$26)") (class "Default")
      (node (ref "U$11") (pin "P$26") (pinfunction "C4_P$26") (pintype "bidirectional"))
    )
    (net (code "74") (name "unconnected-(U$11-P$5-PadP$21)") (class "Default")
      (node (ref "U$11") (pin "P$21") (pinfunction "P$5_P$21") (pintype "bidirectional"))
    )
  )
)
